# Sheet1.net
KiCad netlist of a schematic drawn in Altium Designer
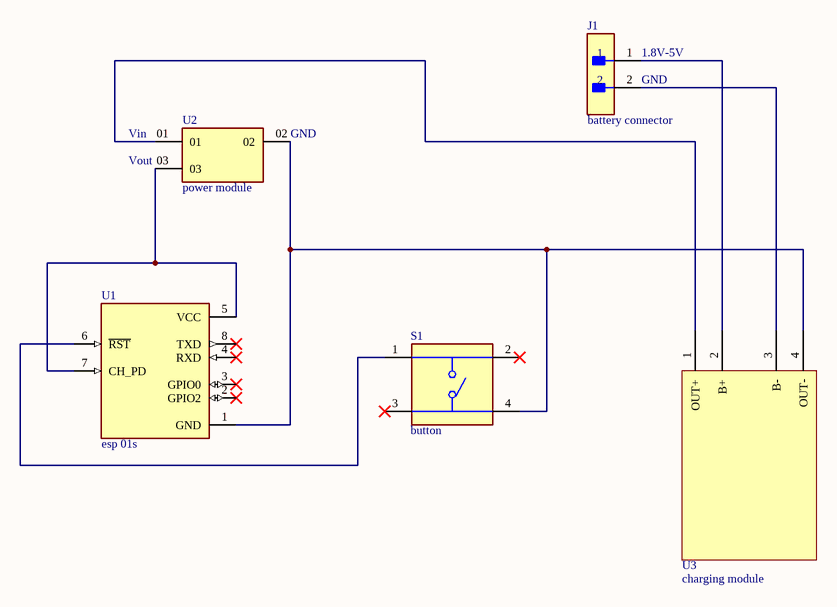
[diagram p0: Sheet1.SchDoc]

(export (version "E")
  (design (tool "Eeschema 10.0.6"))
  (components
    (comp (ref "J1")
      (value "battery connector")
      (footprint "battery connector")
      (libsource (lib "Integrated_Library_button") (part "battery connector"))
    )
    (comp (ref "S1")
      (value "button")
      (footprint "button")
      (libsource (lib "Integrated_Library_button") (part "button"))
    )
    (comp (ref "U1")
      (value "esp 01s")
      (footprint "esp 01s")
      (libsource (lib "Integrated_Library_button") (part "esp 01s"))
    )
    (comp (ref "U2")
      (value "power module")
      (footprint "power module")
      (libsource (lib "Integrated_Library_button") (part "power module"))
    )
    (comp (ref "U3")
      (value "charging module")
      (footprint "charging module")
      (libsource (lib "Integrated_Library_button") (part "charging module"))
    )
  )
  (nets
    (net (code "1") (name "Net-(U1-CH_PD)") (class "Default")
      (node (ref "U1") (pin "5") (pinfunction "VCC_5") (pintype "power_in"))
      (node (ref "U1") (pin "7") (pinfunction "CH_PD_7") (pintype "input"))
      (node (ref "U2") (pin "03") (pinfunction "03_03") (pintype "passive"))
    )
    (net (code "2") (name "Net-(U1-GND)") (class "Default")
      (node (ref "S1") (pin "4") (pinfunction "4_4") (pintype "passive"))
      (node (ref "U1") (pin "1") (pinfunction "GND_1") (pintype "power_in"))
      (node (ref "U2") (pin "02") (pinfunction "02_02") (pintype "passive"))
      (node (ref "U3") (pin "4") (pinfunction "OUT-_4") (pintype "passive"))
    )
    (net (code "3") (name "Net-(U1-~{RST})") (class "Default")
      (node (ref "S1") (pin "1") (pinfunction "1_1") (pintype "passive"))
      (node (ref "U1") (pin "6") (pinfunction "~{RST}_6") (pintype "input"))
    )
    (net (code "4") (name "Net-(U3-B+)") (class "Default")
      (node (ref "J1") (pin "1") (pinfunction "1_1") (pintype "passive"))
      (node (ref "U3") (pin "2") (pinfunction "B+_2") (pintype "passive"))
    )
    (net (code "5") (name "Net-(U3-B-)") (class "Default")
      (node (ref "J1") (pin "2") (pinfunction "2_2") (pintype "passive"))
      (node (ref "U3") (pin "3") (pinfunction "B-_3") (pintype "passive"))
    )
    (net (code "6") (name "Net-(U3-OUT+)") (class "Default")
      (node (ref "U2") (pin "01") (pinfunction "01_01") (pintype "passive"))
      (node (ref "U3") (pin "1") (pinfunction "OUT+_1") (pintype "passive"))
    )
    (net (code "7") (name "unconnected-(S1-Pad2)") (class "Default")
      (node (ref "S1") (pin "2") (pinfunction "2_2") (pintype "passive+no_connect"))
    )
    (net (code "8") (name "unconnected-(S1-Pad3)") (class "Default")
      (node (ref "S1") (pin "3") (pinfunction "3_3") (pintype "passive+no_connect"))
    )
    (net (code "9") (name "unconnected-(U1-GPIO0-Pad3)") (class "Default")
      (node (ref "U1") (pin "3") (pinfunction "GPIO0_3") (pintype "bidirectional+no_connect"))
    )
    (net (code "10") (name "unconnected-(U1-GPIO2-Pad2)") (class "Default")
      (node (ref "U1") (pin "2") (pinfunction "GPIO2_2") (pintype "bidirectional+no_connect"))
    )
    (net (code "11") (name "unconnected-(U1-RXD-Pad4)") (class "Default")
      (node (ref "U1") (pin "4") (pinfunction "RXD_4") (pintype "input+no_connect"))
    )
    (net (code "12") (name "unconnected-(U1-TXD-Pad8)") (class "Default")
      (node (ref "U1") (pin "8") (pinfunction "TXD_8") (pintype "output+no_connect"))
    )
  )
)
